# Nuio_LeftKeyboard_Rev_E_4_UI.net
KiCad netlist of a schematic drawn in Altium Designer
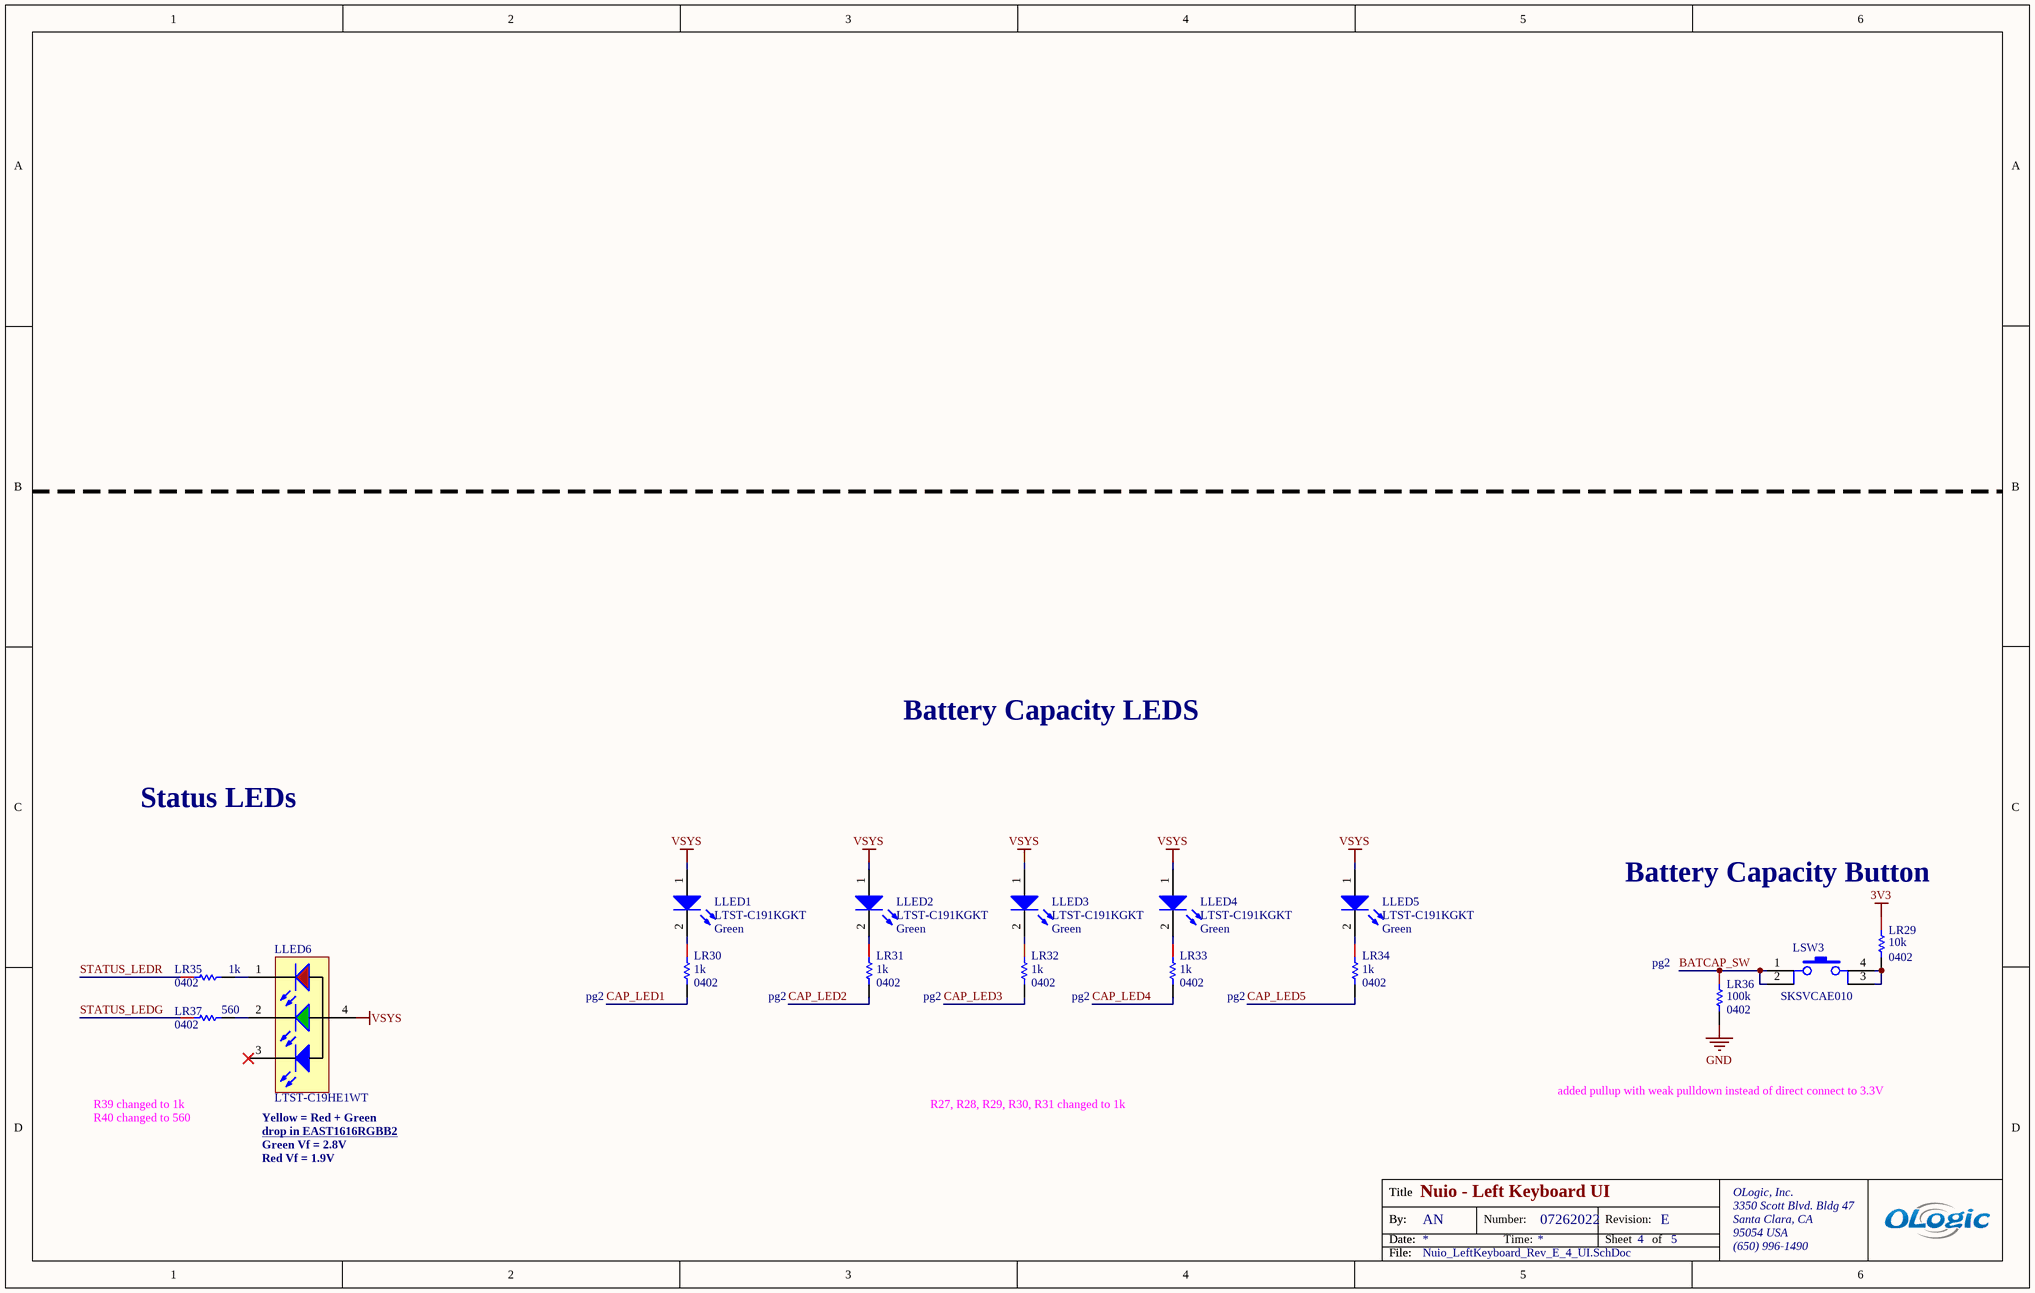
[diagram p0: Nuio_LeftKeyboard_Rev_E_4_UI.SchDoc]

(export (version "E")
  (design (tool "Eeschema 10.0.6"))
  (components
    (comp (ref "LLED1")
      (value "LTST-C191KGKT")
      (footprint "SM-LED-0603")
      (description "LED GREEN CLEAR THIN 0603 SMD")
      (fields
        (field (name "MANUFACTURER PART NUMBER") "LTST-C191KGKT")
        (field (name "COLOR") "Green")
        (field (name "MANUFACTURER") "Lite-On Inc")
      )
      (libsource (lib "OLogic Nexus Vault") (part "OL_LED"))
    )
    (comp (ref "LLED2")
      (value "LTST-C191KGKT")
      (footprint "SM-LED-0603")
      (description "LED GREEN CLEAR THIN 0603 SMD")
      (fields
        (field (name "MANUFACTURER PART NUMBER") "LTST-C191KGKT")
        (field (name "COLOR") "Green")
        (field (name "MANUFACTURER") "Lite-On Inc")
      )
      (libsource (lib "OLogic Nexus Vault") (part "OL_LED"))
    )
    (comp (ref "LLED3")
      (value "LTST-C191KGKT")
      (footprint "SM-LED-0603")
      (description "LED GREEN CLEAR THIN 0603 SMD")
      (fields
        (field (name "MANUFACTURER PART NUMBER") "LTST-C191KGKT")
        (field (name "COLOR") "Green")
        (field (name "MANUFACTURER") "Lite-On Inc")
      )
      (libsource (lib "OLogic Nexus Vault") (part "OL_LED"))
    )
    (comp (ref "LLED4")
      (value "LTST-C191KGKT")
      (footprint "SM-LED-0603")
      (description "LED GREEN CLEAR THIN 0603 SMD")
      (fields
        (field (name "MANUFACTURER PART NUMBER") "LTST-C191KGKT")
        (field (name "COLOR") "Green")
        (field (name "MANUFACTURER") "Lite-On Inc")
      )
      (libsource (lib "OLogic Nexus Vault") (part "OL_LED"))
    )
    (comp (ref "LLED5")
      (value "LTST-C191KGKT")
      (footprint "SM-LED-0603")
      (description "LED GREEN CLEAR THIN 0603 SMD")
      (fields
        (field (name "MANUFACTURER PART NUMBER") "LTST-C191KGKT")
        (field (name "COLOR") "Green")
        (field (name "MANUFACTURER") "Lite-On Inc")
      )
      (libsource (lib "OLogic Nexus Vault") (part "OL_LED"))
    )
    (comp (ref "LLED6")
      (value "LTST-C19HE1WT")
      (footprint "LTST-C19HE1WT")
      (description "LED RGB 605/525/470NM DIFF SMD")
      (fields (field (name "MANUFACTURER") "Lite-On Inc."))
      (libsource (lib "OLogic Nexus Vault") (part "LTST-C19HE1WT"))
    )
    (comp (ref "LR29")
      (value "RES SMD 10K OHM 1% 1/16W 0402")
      (footprint "RESC0402(1005)_L")
      (description "10 kOhms ±1% 0.063W, 1/16W Chip Resistor 0402 (1005 Metric) Thin Film")
      (fields
        (field (name "PACKAGE (IMPERIAL)") "0402")
        (field (name "RESISTANCE") "10k")
        (field (name "POWER") "63mW")
        (field (name "TOLERANCE") "1%")
      )
      (libsource (lib "OLogic Nexus Vault") (part "=Resistance"))
    )
    (comp (ref "LR30")
      (value "RES SMD 1K OHM 1% 1/16W 0402")
      (footprint "RESC0402(1005)_L")
      (fields
        (field (name "RESISTANCE") "1k")
        (field (name "PACKAGE (IMPERIAL)") "0402")
        (field (name "POWER") "63mW")
        (field (name "MANUFACTURER") "Yageo")
        (field (name "TOLERANCE") "1%")
      )
      (libsource (lib "OLogic Nexus Vault") (part "OL_Resistor"))
    )
    (comp (ref "LR31")
      (value "RES SMD 1K OHM 1% 1/16W 0402")
      (footprint "RESC0402(1005)_L")
      (fields
        (field (name "RESISTANCE") "1k")
        (field (name "PACKAGE (IMPERIAL)") "0402")
        (field (name "POWER") "63mW")
        (field (name "MANUFACTURER") "Yageo")
        (field (name "TOLERANCE") "1%")
      )
      (libsource (lib "OLogic Nexus Vault") (part "OL_Resistor"))
    )
    (comp (ref "LR32")
      (value "RES SMD 1K OHM 1% 1/16W 0402")
      (footprint "RESC0402(1005)_L")
      (fields
        (field (name "RESISTANCE") "1k")
        (field (name "PACKAGE (IMPERIAL)") "0402")
        (field (name "POWER") "63mW")
        (field (name "MANUFACTURER") "Yageo")
        (field (name "TOLERANCE") "1%")
      )
      (libsource (lib "OLogic Nexus Vault") (part "OL_Resistor"))
    )
    (comp (ref "LR33")
      (value "RES SMD 1K OHM 1% 1/16W 0402")
      (footprint "RESC0402(1005)_L")
      (fields
        (field (name "RESISTANCE") "1k")
        (field (name "PACKAGE (IMPERIAL)") "0402")
        (field (name "POWER") "63mW")
        (field (name "MANUFACTURER") "Yageo")
        (field (name "TOLERANCE") "1%")
      )
      (libsource (lib "OLogic Nexus Vault") (part "OL_Resistor"))
    )
    (comp (ref "LR34")
      (value "RES SMD 1K OHM 1% 1/16W 0402")
      (footprint "RESC0402(1005)_L")
      (fields
        (field (name "RESISTANCE") "1k")
        (field (name "PACKAGE (IMPERIAL)") "0402")
        (field (name "POWER") "63mW")
        (field (name "MANUFACTURER") "Yageo")
        (field (name "TOLERANCE") "1%")
      )
      (libsource (lib "OLogic Nexus Vault") (part "OL_Resistor"))
    )
    (comp (ref "LR35")
      (value "RES SMD 1K OHM 1% 1/16W 0402")
      (footprint "RESC0402(1005)_L")
      (fields
        (field (name "RESISTANCE") "1k")
        (field (name "PACKAGE (IMPERIAL)") "0402")
        (field (name "POWER") "63mW")
        (field (name "MANUFACTURER") "Yageo")
        (field (name "TOLERANCE") "1%")
      )
      (libsource (lib "OLogic Nexus Vault") (part "OL_Resistor"))
    )
    (comp (ref "LR36")
      (value "100k")
      (footprint "RESC0402(1005)_L")
      (description "±1% 0.063W, 1/16W Chip Resistor 0402 (1005 Metric) Moisture Resistant Thick Film")
      (fields
        (field (name "CASE CODE (IMPERIAL)") "0402")
        (field (name "TOLERANCE") "1%")
        (field (name "MANUFACTURER") "YAGEO")
      )
      (libsource (lib "OLogic Nexus Vault") (part "=Resistance"))
    )
    (comp (ref "LR37")
      (value "560")
      (footprint "RESC0402(1005)_L")
      (description "RES SMD 560 OHM 1% 1/16W 0402")
      (fields
        (field (name "PACKAGE (IMPERIAL)") "0402")
        (field (name "POWER") "63mW")
        (field (name "RESISTANCE") "560")
        (field (name "TOLERANCE") "1%")
      )
      (libsource (lib "OLogic Nexus Vault") (part "=Resistance"))
    )
    (comp (ref "LSW3")
      (value "SKSVCAE010")
      (footprint "SKSVCAE010")
      (description "2.8x1.9mm Compact Type with Projection Surface Mount SKSV Series Tact Switch")
      (fields (field (name "MANUFACTURER") "Alps Alpine"))
      (libsource (lib "OLogic Nexus Vault") (part "OL_Switch_Tactile_4"))
    )
  )
  (nets
    (net (code "1") (name "/BATCAP_SW") (class "Default")
      (node (ref "LR36") (pin "1") (pinfunction "1_1") (pintype "passive"))
      (node (ref "LSW3") (pin "1") (pinfunction "1_1") (pintype "passive"))
      (node (ref "LSW3") (pin "2") (pinfunction "2_2") (pintype "passive"))
    )
    (net (code "2") (name "/CAP_LED1") (class "Default")
      (node (ref "LR30") (pin "2") (pinfunction "2_2") (pintype "passive"))
    )
    (net (code "3") (name "/CAP_LED2") (class "Default")
      (node (ref "LR31") (pin "2") (pinfunction "2_2") (pintype "passive"))
    )
    (net (code "4") (name "/CAP_LED3") (class "Default")
      (node (ref "LR32") (pin "2") (pinfunction "2_2") (pintype "passive"))
    )
    (net (code "5") (name "/CAP_LED4") (class "Default")
      (node (ref "LR33") (pin "2") (pinfunction "2_2") (pintype "passive"))
    )
    (net (code "6") (name "/CAP_LED5") (class "Default")
      (node (ref "LR34") (pin "2") (pinfunction "2_2") (pintype "passive"))
    )
    (net (code "7") (name "/STATUS_LEDG") (class "Default")
      (node (ref "LR37") (pin "1") (pinfunction "1_1") (pintype "passive"))
    )
    (net (code "8") (name "/STATUS_LEDR") (class "Default")
      (node (ref "LR35") (pin "1") (pinfunction "1_1") (pintype "passive"))
    )
    (net (code "9") (name "3V3") (class "Default")
      (node (ref "LR29") (pin "1") (pinfunction "1_1") (pintype "passive"))
    )
    (net (code "10") (name "GND") (class "Default")
      (node (ref "LR36") (pin "2") (pinfunction "2_2") (pintype "passive"))
    )
    (net (code "11") (name "Net-(LLED1-K)") (class "Default")
      (node (ref "LLED1") (pin "2") (pinfunction "K_2") (pintype "passive"))
      (node (ref "LR30") (pin "1") (pinfunction "1_1") (pintype "passive"))
    )
    (net (code "12") (name "Net-(LLED2-K)") (class "Default")
      (node (ref "LLED2") (pin "2") (pinfunction "K_2") (pintype "passive"))
      (node (ref "LR31") (pin "1") (pinfunction "1_1") (pintype "passive"))
    )
    (net (code "13") (name "Net-(LLED3-K)") (class "Default")
      (node (ref "LLED3") (pin "2") (pinfunction "K_2") (pintype "passive"))
      (node (ref "LR32") (pin "1") (pinfunction "1_1") (pintype "passive"))
    )
    (net (code "14") (name "Net-(LLED4-K)") (class "Default")
      (node (ref "LLED4") (pin "2") (pinfunction "K_2") (pintype "passive"))
      (node (ref "LR33") (pin "1") (pinfunction "1_1") (pintype "passive"))
    )
    (net (code "15") (name "Net-(LLED5-K)") (class "Default")
      (node (ref "LLED5") (pin "2") (pinfunction "K_2") (pintype "passive"))
      (node (ref "LR34") (pin "1") (pinfunction "1_1") (pintype "passive"))
    )
    (net (code "16") (name "Net-(LLED6-G)") (class "Default")
      (node (ref "LLED6") (pin "2") (pinfunction "G_2") (pintype "passive"))
      (node (ref "LR37") (pin "2") (pinfunction "2_2") (pintype "passive"))
    )
    (net (code "17") (name "Net-(LLED6-R)") (class "Default")
      (node (ref "LLED6") (pin "1") (pinfunction "R_1") (pintype "passive"))
      (node (ref "LR35") (pin "2") (pinfunction "2_2") (pintype "passive"))
    )
    (net (code "18") (name "Net-(LR29-Pad2)") (class "Default")
      (node (ref "LR29") (pin "2") (pinfunction "2_2") (pintype "passive"))
      (node (ref "LSW3") (pin "3") (pinfunction "3_3") (pintype "passive"))
      (node (ref "LSW3") (pin "4") (pinfunction "4_4") (pintype "passive"))
    )
    (net (code "19") (name "VSYS") (class "Default")
      (node (ref "LLED1") (pin "1") (pinfunction "A_1") (pintype "passive"))
      (node (ref "LLED2") (pin "1") (pinfunction "A_1") (pintype "passive"))
      (node (ref "LLED3") (pin "1") (pinfunction "A_1") (pintype "passive"))
      (node (ref "LLED4") (pin "1") (pinfunction "A_1") (pintype "passive"))
      (node (ref "LLED5") (pin "1") (pinfunction "A_1") (pintype "passive"))
      (node (ref "LLED6") (pin "4") (pinfunction "Anode_4") (pintype "passive"))
    )
    (net (code "20") (name "unconnected-(LLED6-B-Pad3)") (class "Default")
      (node (ref "LLED6") (pin "3") (pinfunction "B_3") (pintype "passive+no_connect"))
    )
  )
)
